# Firefly-Bottom.net
KiCad netlist of a schematic drawn in EAGLE
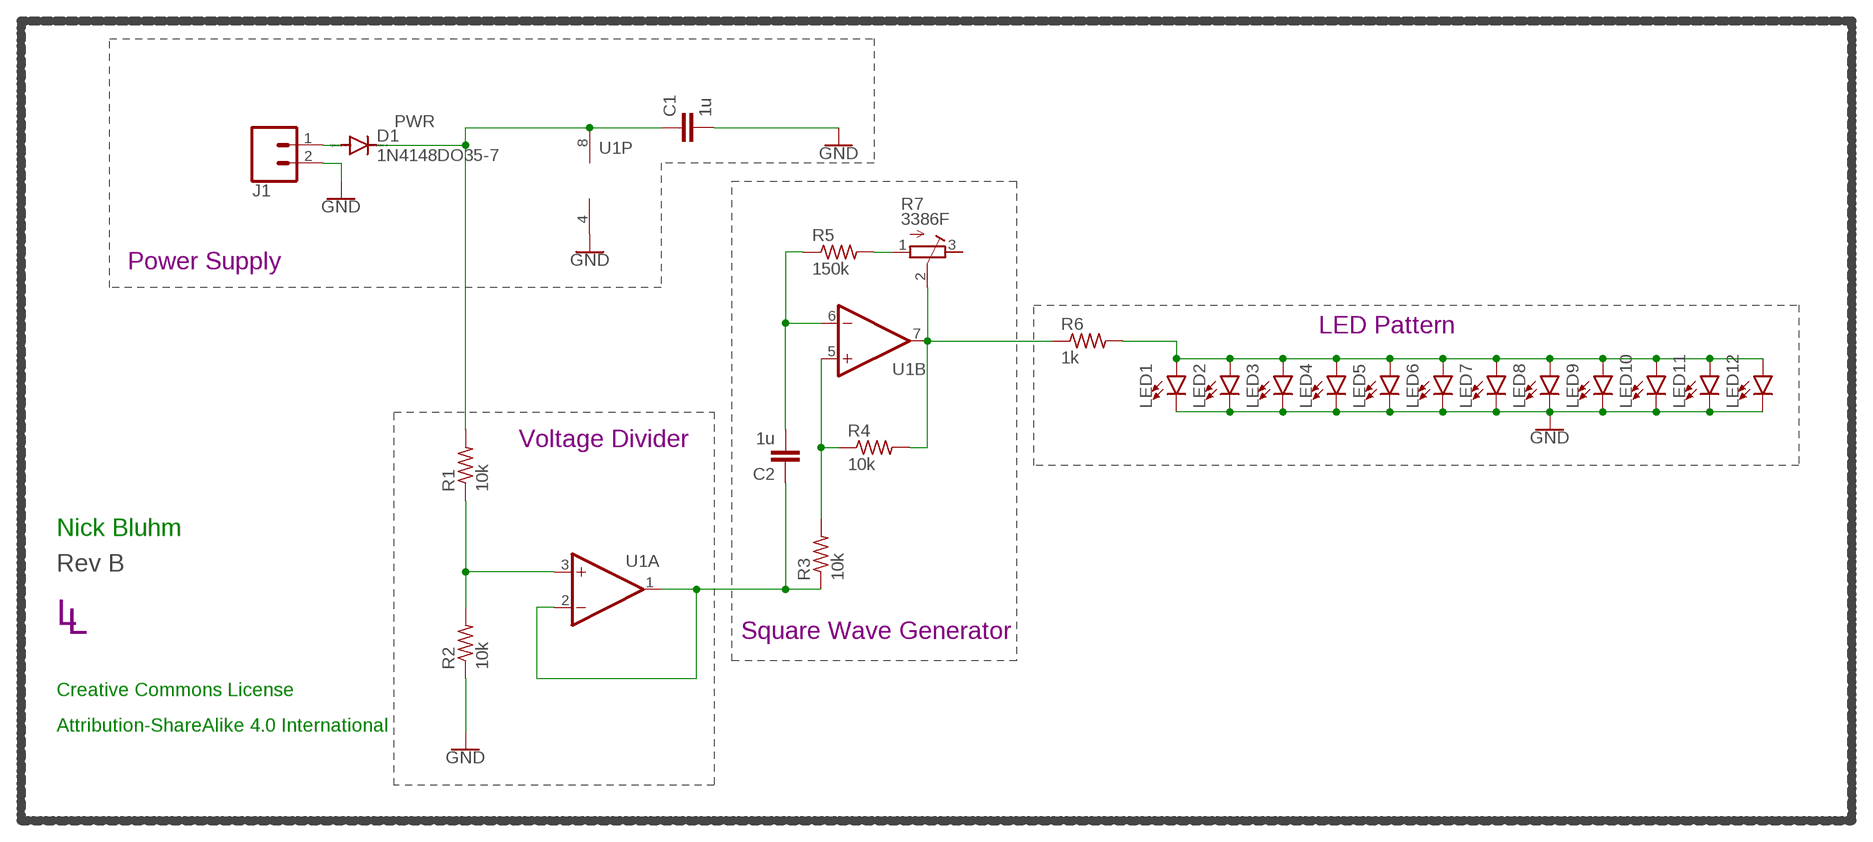
[diagram p0: schematic, sheet 1]

(export (version "E")
  (design (tool "Eeschema 10.0.6"))
  (components
    (comp (ref "C1")
      (value "1u")
      (footprint "eagle-import:C0805")
      (libsource (lib "eagle-import") (part "CAPACITOR0805"))
    )
    (comp (ref "C2")
      (value "1u")
      (footprint "eagle-import:C0805")
      (libsource (lib "eagle-import") (part "CAPACITOR0805"))
    )
    (comp (ref "D1")
      (value "1N4148DO35-7")
      (footprint "eagle-import:DO35-7")
      (libsource (lib "eagle-import") (part "1N4148DO35-7"))
    )
    (comp (ref "J1")
      (value "CONN_02")
      (footprint "eagle-import:1X02")
      (libsource (lib "eagle-import") (part "CONN_02"))
    )
    (comp (ref "LED1")
      (value "LED5MM")
      (footprint "eagle-import:LED_5MM")
      (libsource (lib "eagle-import") (part "LED5MM"))
    )
    (comp (ref "LED2")
      (value "LED5MM")
      (footprint "eagle-import:LED_5MM")
      (libsource (lib "eagle-import") (part "LED5MM"))
    )
    (comp (ref "LED3")
      (value "LED5MM")
      (footprint "eagle-import:LED_5MM")
      (libsource (lib "eagle-import") (part "LED5MM"))
    )
    (comp (ref "LED4")
      (value "LED5MM")
      (footprint "eagle-import:LED_5MM")
      (libsource (lib "eagle-import") (part "LED5MM"))
    )
    (comp (ref "LED5")
      (value "LED5MM")
      (footprint "eagle-import:LED_5MM")
      (libsource (lib "eagle-import") (part "LED5MM"))
    )
    (comp (ref "LED6")
      (value "LED5MM")
      (footprint "eagle-import:LED_5MM")
      (libsource (lib "eagle-import") (part "LED5MM"))
    )
    (comp (ref "LED7")
      (value "LED5MM")
      (footprint "eagle-import:LED_5MM")
      (libsource (lib "eagle-import") (part "LED5MM"))
    )
    (comp (ref "LED8")
      (value "LED5MM")
      (footprint "eagle-import:LED_5MM")
      (libsource (lib "eagle-import") (part "LED5MM"))
    )
    (comp (ref "LED9")
      (value "LED5MM")
      (footprint "eagle-import:LED_5MM")
      (libsource (lib "eagle-import") (part "LED5MM"))
    )
    (comp (ref "LED10")
      (value "LED5MM")
      (footprint "eagle-import:LED_5MM")
      (libsource (lib "eagle-import") (part "LED5MM"))
    )
    (comp (ref "LED11")
      (value "LED5MM")
      (footprint "eagle-import:LED_5MM")
      (libsource (lib "eagle-import") (part "LED5MM"))
    )
    (comp (ref "LED12")
      (value "LED5MM")
      (footprint "eagle-import:LED_5MM")
      (libsource (lib "eagle-import") (part "LED5MM"))
    )
    (comp (ref "R1")
      (value "10k")
      (footprint "eagle-import:R0805")
      (libsource (lib "eagle-import") (part "RESISTOR0805"))
    )
    (comp (ref "R2")
      (value "10k")
      (footprint "eagle-import:R0805")
      (libsource (lib "eagle-import") (part "RESISTOR0805"))
    )
    (comp (ref "R3")
      (value "10k")
      (footprint "eagle-import:R0805")
      (libsource (lib "eagle-import") (part "RESISTOR0805"))
    )
    (comp (ref "R4")
      (value "10k")
      (footprint "eagle-import:R0805")
      (libsource (lib "eagle-import") (part "RESISTOR0805"))
    )
    (comp (ref "R5")
      (value "150k")
      (footprint "eagle-import:R0805")
      (libsource (lib "eagle-import") (part "RESISTOR0805"))
    )
    (comp (ref "R6")
      (value "1k")
      (footprint "eagle-import:R0805")
      (libsource (lib "eagle-import") (part "RESISTOR0805"))
    )
    (comp (ref "R7")
      (value "3386F")
      (footprint "eagle-import:3386F-FOOTPRINT")
      (libsource (lib "eagle-import") (part "3386F"))
    )
    (comp (ref "U$4")
      (value "REVISION.B")
      (footprint "eagle-import:REV.B")
      (libsource (lib "eagle-import") (part "REVISION.B"))
    )
    (comp (ref "U$5")
      (value "LINNES.LAB.LOGO")
      (footprint "eagle-import:LINNES.LAB.LOGO")
      (libsource (lib "eagle-import") (part "LINNES.LAB.LOGO"))
    )
    (comp (ref "U1")
      (value "OP-DUALMCP6002R")
      (footprint "eagle-import:SO8")
      (fields (field (name "MF") "Microchip Technology") (field (name "MPN") "MCP6002T-I/SN"))
      (libsource (lib "eagle-import") (part "OP-DUALRMCP6002"))
    )
  )
  (nets
    (net (code "1") (name "/PWR") (class "Default")
      (node (ref "C1") (pin "1") (pinfunction "1_1") (pintype "passive"))
      (node (ref "D1") (pin "C") (pinfunction "C_C") (pintype "passive"))
      (node (ref "R1") (pin "2") (pinfunction "2_2") (pintype "passive"))
      (node (ref "U1") (pin "8") (pinfunction "V+_8") (pintype "power_in"))
    )
    (net (code "2") (name "GND") (class "Default")
      (node (ref "C1") (pin "2") (pinfunction "2_2") (pintype "passive"))
      (node (ref "J1") (pin "2") (pinfunction "2_2") (pintype "passive"))
      (node (ref "LED1") (pin "K") (pinfunction "C_K") (pintype "passive"))
      (node (ref "LED10") (pin "K") (pinfunction "C_K") (pintype "passive"))
      (node (ref "LED11") (pin "K") (pinfunction "C_K") (pintype "passive"))
      (node (ref "LED12") (pin "K") (pinfunction "C_K") (pintype "passive"))
      (node (ref "LED2") (pin "K") (pinfunction "C_K") (pintype "passive"))
      (node (ref "LED3") (pin "K") (pinfunction "C_K") (pintype "passive"))
      (node (ref "LED4") (pin "K") (pinfunction "C_K") (pintype "passive"))
      (node (ref "LED5") (pin "K") (pinfunction "C_K") (pintype "passive"))
      (node (ref "LED6") (pin "K") (pinfunction "C_K") (pintype "passive"))
      (node (ref "LED7") (pin "K") (pinfunction "C_K") (pintype "passive"))
      (node (ref "LED8") (pin "K") (pinfunction "C_K") (pintype "passive"))
      (node (ref "LED9") (pin "K") (pinfunction "C_K") (pintype "passive"))
      (node (ref "R2") (pin "1") (pinfunction "1_1") (pintype "passive"))
      (node (ref "U1") (pin "4") (pinfunction "V-_4") (pintype "power_in"))
    )
    (net (code "3") (name "Net-(D1-PadA)") (class "Default")
      (node (ref "D1") (pin "A") (pinfunction "A_A") (pintype "passive"))
      (node (ref "J1") (pin "1") (pinfunction "1_1") (pintype "passive"))
    )
    (net (code "4") (name "Net-(LED1-PadA)") (class "Default")
      (node (ref "LED1") (pin "A") (pinfunction "A_A") (pintype "passive"))
      (node (ref "LED10") (pin "A") (pinfunction "A_A") (pintype "passive"))
      (node (ref "LED11") (pin "A") (pinfunction "A_A") (pintype "passive"))
      (node (ref "LED12") (pin "A") (pinfunction "A_A") (pintype "passive"))
      (node (ref "LED2") (pin "A") (pinfunction "A_A") (pintype "passive"))
      (node (ref "LED3") (pin "A") (pinfunction "A_A") (pintype "passive"))
      (node (ref "LED4") (pin "A") (pinfunction "A_A") (pintype "passive"))
      (node (ref "LED5") (pin "A") (pinfunction "A_A") (pintype "passive"))
      (node (ref "LED6") (pin "A") (pinfunction "A_A") (pintype "passive"))
      (node (ref "LED7") (pin "A") (pinfunction "A_A") (pintype "passive"))
      (node (ref "LED8") (pin "A") (pinfunction "A_A") (pintype "passive"))
      (node (ref "LED9") (pin "A") (pinfunction "A_A") (pintype "passive"))
      (node (ref "R6") (pin "2") (pinfunction "2_2") (pintype "passive"))
    )
    (net (code "5") (name "Net-(R7-A)") (class "Default")
      (node (ref "R5") (pin "2") (pinfunction "2_2") (pintype "passive"))
      (node (ref "R7") (pin "1") (pinfunction "A_1") (pintype "passive"))
    )
    (net (code "6") (name "Net-(R7-W)") (class "Default")
      (node (ref "R4") (pin "2") (pinfunction "2_2") (pintype "passive"))
      (node (ref "R6") (pin "1") (pinfunction "1_1") (pintype "passive"))
      (node (ref "R7") (pin "2") (pinfunction "W_2") (pintype "passive"))
      (node (ref "U1") (pin "7") (pinfunction "OUT_7") (pintype "output"))
    )
    (net (code "7") (name "Net-(U1A-+IN)") (class "Default")
      (node (ref "R1") (pin "1") (pinfunction "1_1") (pintype "passive"))
      (node (ref "R2") (pin "2") (pinfunction "2_2") (pintype "passive"))
      (node (ref "U1") (pin "3") (pinfunction "+IN_3") (pintype "input"))
    )
    (net (code "8") (name "Net-(U1A--IN)") (class "Default")
      (node (ref "C2") (pin "1") (pinfunction "1_1") (pintype "passive"))
      (node (ref "R3") (pin "1") (pinfunction "1_1") (pintype "passive"))
      (node (ref "U1") (pin "1") (pinfunction "OUT_1") (pintype "output"))
      (node (ref "U1") (pin "2") (pinfunction "-IN_2") (pintype "input"))
    )
    (net (code "9") (name "Net-(U1B-+IN)") (class "Default")
      (node (ref "R3") (pin "2") (pinfunction "2_2") (pintype "passive"))
      (node (ref "R4") (pin "1") (pinfunction "1_1") (pintype "passive"))
      (node (ref "U1") (pin "5") (pinfunction "+IN_5") (pintype "input"))
    )
    (net (code "10") (name "Net-(U1B--IN)") (class "Default")
      (node (ref "C2") (pin "2") (pinfunction "2_2") (pintype "passive"))
      (node (ref "R5") (pin "1") (pinfunction "1_1") (pintype "passive"))
      (node (ref "U1") (pin "6") (pinfunction "-IN_6") (pintype "input"))
    )
    (net (code "11") (name "unconnected-(R7-E-Pad3)") (class "Default")
      (node (ref "R7") (pin "3") (pinfunction "E_3") (pintype "passive"))
    )
  )
)
